# Board_2.net
KiCad netlist of a schematic drawn in EAGLE
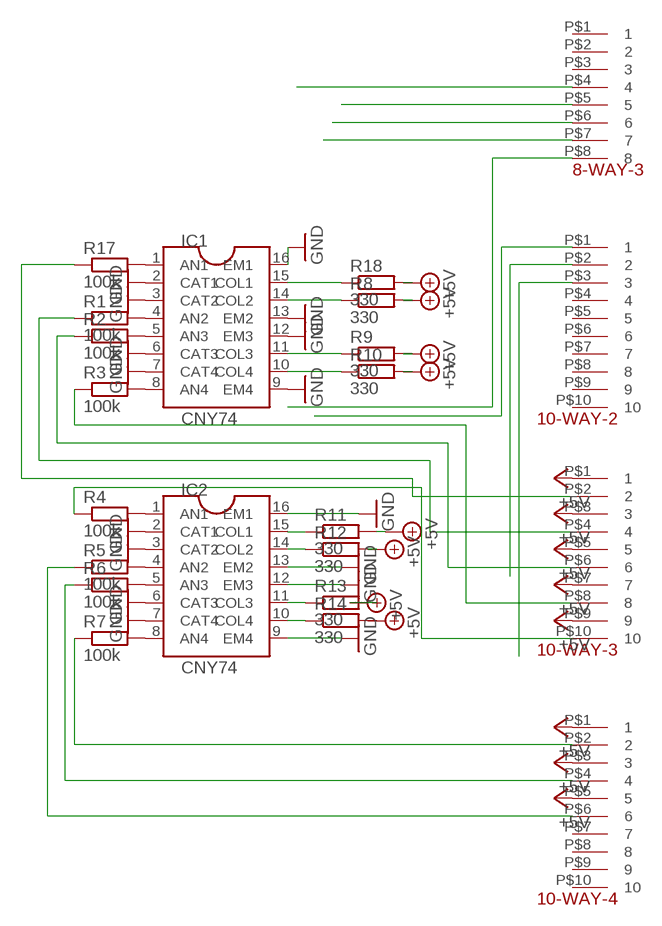
[diagram p0: schematic, sheet 1]

(export (version "E")
  (design (tool "Eeschema 10.0.6"))
  (components
    (comp (ref "8-WAY-3")
      (value "SDH8PIN")
      (footprint "eagle-import:SDH8PIN")
      (libsource (lib "eagle-import") (part "SDH8PIN"))
    )
    (comp (ref "10-WAY-2")
      (value "SDH10PIN")
      (footprint "eagle-import:SDH10PIN")
      (libsource (lib "eagle-import") (part "SDH10PIN"))
    )
    (comp (ref "10-WAY-3")
      (value "SDH10PIN")
      (footprint "eagle-import:SDH10PIN")
      (libsource (lib "eagle-import") (part "SDH10PIN"))
    )
    (comp (ref "10-WAY-4")
      (value "SDH10PIN")
      (footprint "eagle-import:SDH10PIN")
      (libsource (lib "eagle-import") (part "SDH10PIN"))
    )
    (comp (ref "IC1")
      (value "IC-CNY74-16DIL")
      (footprint "eagle-import:IC-CNY74-16DIL")
      (libsource (lib "eagle-import") (part "IC-CNY74-16DIL"))
    )
    (comp (ref "IC2")
      (value "IC-CNY74-16DIL")
      (footprint "eagle-import:IC-CNY74-16DIL")
      (libsource (lib "eagle-import") (part "IC-CNY74-16DIL"))
    )
    (comp (ref "R1")
      (value "100k")
      (footprint "eagle-import:P0613V")
      (libsource (lib "eagle-import") (part "R-EU_0613/5V"))
    )
    (comp (ref "R2")
      (value "100k")
      (footprint "eagle-import:P0613V")
      (libsource (lib "eagle-import") (part "R-EU_0613/5V"))
    )
    (comp (ref "R3")
      (value "100k")
      (footprint "eagle-import:P0613V")
      (libsource (lib "eagle-import") (part "R-EU_0613/5V"))
    )
    (comp (ref "R4")
      (value "100k")
      (footprint "eagle-import:P0613V")
      (libsource (lib "eagle-import") (part "R-EU_0613/5V"))
    )
    (comp (ref "R5")
      (value "100k")
      (footprint "eagle-import:P0613V")
      (libsource (lib "eagle-import") (part "R-EU_0613/5V"))
    )
    (comp (ref "R6")
      (value "100k")
      (footprint "eagle-import:P0613V")
      (libsource (lib "eagle-import") (part "R-EU_0613/5V"))
    )
    (comp (ref "R7")
      (value "100k")
      (footprint "eagle-import:P0613V")
      (libsource (lib "eagle-import") (part "R-EU_0613/5V"))
    )
    (comp (ref "R8")
      (value "330")
      (footprint "eagle-import:P0613V")
      (libsource (lib "eagle-import") (part "R-EU_0613/5V"))
    )
    (comp (ref "R9")
      (value "330")
      (footprint "eagle-import:P0613V")
      (libsource (lib "eagle-import") (part "R-EU_0613/5V"))
    )
    (comp (ref "R10")
      (value "330")
      (footprint "eagle-import:P0613V")
      (libsource (lib "eagle-import") (part "R-EU_0613/5V"))
    )
    (comp (ref "R11")
      (value "330")
      (footprint "eagle-import:P0613V")
      (libsource (lib "eagle-import") (part "R-EU_0613/5V"))
    )
    (comp (ref "R12")
      (value "330")
      (footprint "eagle-import:P0613V")
      (libsource (lib "eagle-import") (part "R-EU_0613/5V"))
    )
    (comp (ref "R13")
      (value "330")
      (footprint "eagle-import:P0613V")
      (libsource (lib "eagle-import") (part "R-EU_0613/5V"))
    )
    (comp (ref "R14")
      (value "330")
      (footprint "eagle-import:P0613V")
      (libsource (lib "eagle-import") (part "R-EU_0613/5V"))
    )
    (comp (ref "R17")
      (value "100k")
      (footprint "eagle-import:P0613V")
      (libsource (lib "eagle-import") (part "R-EU_0613/5V"))
    )
    (comp (ref "R18")
      (value "330")
      (footprint "eagle-import:P0613V")
      (libsource (lib "eagle-import") (part "R-EU_0613/5V"))
    )
  )
  (nets
    (net (code "1") (name "+5V") (class "Default")
      (node (ref "10-WAY-3") (pin "P$1") (pinfunction "1_P$1") (pintype "bidirectional"))
      (node (ref "10-WAY-3") (pin "P$3") (pinfunction "3_P$3") (pintype "bidirectional"))
      (node (ref "10-WAY-3") (pin "P$5") (pinfunction "5_P$5") (pintype "bidirectional"))
      (node (ref "10-WAY-3") (pin "P$7") (pinfunction "7_P$7") (pintype "bidirectional"))
      (node (ref "10-WAY-3") (pin "P$9") (pinfunction "9_P$9") (pintype "bidirectional"))
      (node (ref "10-WAY-4") (pin "P$1") (pinfunction "1_P$1") (pintype "bidirectional"))
      (node (ref "10-WAY-4") (pin "P$3") (pinfunction "3_P$3") (pintype "bidirectional"))
      (node (ref "10-WAY-4") (pin "P$5") (pinfunction "5_P$5") (pintype "bidirectional"))
      (node (ref "R10") (pin "2") (pinfunction "2_2") (pintype "passive"))
      (node (ref "R11") (pin "2") (pinfunction "2_2") (pintype "passive"))
      (node (ref "R12") (pin "2") (pinfunction "2_2") (pintype "passive"))
      (node (ref "R13") (pin "2") (pinfunction "2_2") (pintype "passive"))
      (node (ref "R18") (pin "2") (pinfunction "2_2") (pintype "passive"))
      (node (ref "R8") (pin "2") (pinfunction "2_2") (pintype "passive"))
      (node (ref "R9") (pin "2") (pinfunction "2_2") (pintype "passive"))
    )
    (net (code "2") (name "GND") (class "Default")
      (node (ref "IC1") (pin "12") (pinfunction "EM3_12") (pintype "bidirectional"))
      (node (ref "IC1") (pin "13") (pinfunction "EM2_13") (pintype "bidirectional"))
      (node (ref "IC1") (pin "16") (pinfunction "EM1_16") (pintype "bidirectional"))
      (node (ref "IC1") (pin "2") (pinfunction "CAT1_2") (pintype "bidirectional"))
      (node (ref "IC1") (pin "3") (pinfunction "CAT2_3") (pintype "bidirectional"))
      (node (ref "IC1") (pin "6") (pinfunction "CAT3_6") (pintype "bidirectional"))
      (node (ref "IC1") (pin "7") (pinfunction "CAT4_7") (pintype "bidirectional"))
      (node (ref "IC1") (pin "9") (pinfunction "EM4_9") (pintype "bidirectional"))
      (node (ref "IC2") (pin "12") (pinfunction "EM3_12") (pintype "bidirectional"))
      (node (ref "IC2") (pin "13") (pinfunction "EM2_13") (pintype "bidirectional"))
      (node (ref "IC2") (pin "16") (pinfunction "EM1_16") (pintype "bidirectional"))
      (node (ref "IC2") (pin "2") (pinfunction "CAT1_2") (pintype "bidirectional"))
      (node (ref "IC2") (pin "3") (pinfunction "CAT2_3") (pintype "bidirectional"))
      (node (ref "IC2") (pin "6") (pinfunction "CAT3_6") (pintype "bidirectional"))
      (node (ref "IC2") (pin "7") (pinfunction "CAT4_7") (pintype "bidirectional"))
      (node (ref "IC2") (pin "9") (pinfunction "EM4_9") (pintype "bidirectional"))
    )
    (net (code "3") (name "Net-(10-WAY-3-2)") (class "Default")
      (node (ref "10-WAY-3") (pin "P$2") (pinfunction "2_P$2") (pintype "bidirectional"))
      (node (ref "R17") (pin "1") (pinfunction "1_1") (pintype "passive"))
    )
    (net (code "4") (name "Net-(10-WAY-3-4)") (class "Default")
      (node (ref "10-WAY-3") (pin "P$4") (pinfunction "4_P$4") (pintype "bidirectional"))
      (node (ref "R1") (pin "1") (pinfunction "1_1") (pintype "passive"))
    )
    (net (code "5") (name "Net-(10-WAY-3-6)") (class "Default")
      (node (ref "10-WAY-3") (pin "P$6") (pinfunction "6_P$6") (pintype "bidirectional"))
      (node (ref "R2") (pin "1") (pinfunction "1_1") (pintype "passive"))
    )
    (net (code "6") (name "Net-(10-WAY-3-8)") (class "Default")
      (node (ref "10-WAY-3") (pin "P$8") (pinfunction "8_P$8") (pintype "bidirectional"))
      (node (ref "R3") (pin "1") (pinfunction "1_1") (pintype "passive"))
    )
    (net (code "7") (name "Net-(10-WAY-3-10)") (class "Default")
      (node (ref "10-WAY-3") (pin "P$10") (pinfunction "10_P$10") (pintype "bidirectional"))
      (node (ref "R4") (pin "1") (pinfunction "1_1") (pintype "passive"))
    )
    (net (code "8") (name "Net-(10-WAY-4-2)") (class "Default")
      (node (ref "10-WAY-4") (pin "P$2") (pinfunction "2_P$2") (pintype "bidirectional"))
      (node (ref "R7") (pin "1") (pinfunction "1_1") (pintype "passive"))
    )
    (net (code "9") (name "Net-(10-WAY-4-4)") (class "Default")
      (node (ref "10-WAY-4") (pin "P$4") (pinfunction "4_P$4") (pintype "bidirectional"))
      (node (ref "R6") (pin "1") (pinfunction "1_1") (pintype "passive"))
    )
    (net (code "10") (name "Net-(10-WAY-4-6)") (class "Default")
      (node (ref "10-WAY-4") (pin "P$6") (pinfunction "6_P$6") (pintype "bidirectional"))
      (node (ref "R5") (pin "1") (pinfunction "1_1") (pintype "passive"))
    )
    (net (code "11") (name "Net-(IC1-AN1)") (class "Default")
      (node (ref "IC1") (pin "1") (pinfunction "AN1_1") (pintype "bidirectional"))
      (node (ref "R17") (pin "2") (pinfunction "2_2") (pintype "passive"))
    )
    (net (code "12") (name "Net-(IC1-AN2)") (class "Default")
      (node (ref "IC1") (pin "4") (pinfunction "AN2_4") (pintype "bidirectional"))
      (node (ref "R1") (pin "2") (pinfunction "2_2") (pintype "passive"))
    )
    (net (code "13") (name "Net-(IC1-AN3)") (class "Default")
      (node (ref "IC1") (pin "5") (pinfunction "AN3_5") (pintype "bidirectional"))
      (node (ref "R2") (pin "2") (pinfunction "2_2") (pintype "passive"))
    )
    (net (code "14") (name "Net-(IC1-AN4)") (class "Default")
      (node (ref "IC1") (pin "8") (pinfunction "AN4_8") (pintype "bidirectional"))
      (node (ref "R3") (pin "2") (pinfunction "2_2") (pintype "passive"))
    )
    (net (code "15") (name "Net-(IC1-COL1)") (class "Default")
      (node (ref "IC1") (pin "15") (pinfunction "COL1_15") (pintype "bidirectional"))
      (node (ref "R18") (pin "1") (pinfunction "1_1") (pintype "passive"))
    )
    (net (code "16") (name "Net-(IC1-COL2)") (class "Default")
      (node (ref "IC1") (pin "14") (pinfunction "COL2_14") (pintype "bidirectional"))
      (node (ref "R8") (pin "1") (pinfunction "1_1") (pintype "passive"))
    )
    (net (code "17") (name "Net-(IC1-COL3)") (class "Default")
      (node (ref "IC1") (pin "11") (pinfunction "COL3_11") (pintype "bidirectional"))
      (node (ref "R9") (pin "1") (pinfunction "1_1") (pintype "passive"))
    )
    (net (code "18") (name "Net-(IC1-COL4)") (class "Default")
      (node (ref "IC1") (pin "10") (pinfunction "COL4_10") (pintype "bidirectional"))
      (node (ref "R10") (pin "1") (pinfunction "1_1") (pintype "passive"))
    )
    (net (code "19") (name "Net-(IC2-AN1)") (class "Default")
      (node (ref "IC2") (pin "1") (pinfunction "AN1_1") (pintype "bidirectional"))
      (node (ref "R4") (pin "2") (pinfunction "2_2") (pintype "passive"))
    )
    (net (code "20") (name "Net-(IC2-AN2)") (class "Default")
      (node (ref "IC2") (pin "4") (pinfunction "AN2_4") (pintype "bidirectional"))
      (node (ref "R5") (pin "2") (pinfunction "2_2") (pintype "passive"))
    )
    (net (code "21") (name "Net-(IC2-AN3)") (class "Default")
      (node (ref "IC2") (pin "5") (pinfunction "AN3_5") (pintype "bidirectional"))
      (node (ref "R6") (pin "2") (pinfunction "2_2") (pintype "passive"))
    )
    (net (code "22") (name "Net-(IC2-AN4)") (class "Default")
      (node (ref "IC2") (pin "8") (pinfunction "AN4_8") (pintype "bidirectional"))
      (node (ref "R7") (pin "2") (pinfunction "2_2") (pintype "passive"))
    )
    (net (code "23") (name "Net-(IC2-COL1)") (class "Default")
      (node (ref "IC2") (pin "15") (pinfunction "COL1_15") (pintype "bidirectional"))
      (node (ref "R11") (pin "1") (pinfunction "1_1") (pintype "passive"))
    )
    (net (code "24") (name "Net-(IC2-COL2)") (class "Default")
      (node (ref "IC2") (pin "14") (pinfunction "COL2_14") (pintype "bidirectional"))
      (node (ref "R12") (pin "1") (pinfunction "1_1") (pintype "passive"))
    )
    (net (code "25") (name "Net-(IC2-COL3)") (class "Default")
      (node (ref "IC2") (pin "11") (pinfunction "COL3_11") (pintype "bidirectional"))
      (node (ref "R13") (pin "1") (pinfunction "1_1") (pintype "passive"))
    )
    (net (code "26") (name "Net-(IC2-COL4)") (class "Default")
      (node (ref "IC2") (pin "10") (pinfunction "COL4_10") (pintype "bidirectional"))
      (node (ref "R14") (pin "1") (pinfunction "1_1") (pintype "passive"))
    )
    (net (code "27") (name "unconnected-(8-WAY-3-1-PadP$1)") (class "Default")
      (node (ref "8-WAY-3") (pin "P$1") (pinfunction "1_P$1") (pintype "bidirectional"))
    )
    (net (code "28") (name "unconnected-(8-WAY-3-2-PadP$2)") (class "Default")
      (node (ref "8-WAY-3") (pin "P$2") (pinfunction "2_P$2") (pintype "bidirectional"))
    )
    (net (code "29") (name "unconnected-(8-WAY-3-3-PadP$3)") (class "Default")
      (node (ref "8-WAY-3") (pin "P$3") (pinfunction "3_P$3") (pintype "bidirectional"))
    )
    (net (code "30") (name "unconnected-(8-WAY-3-4-PadP$4)") (class "Default")
      (node (ref "8-WAY-3") (pin "P$4") (pinfunction "4_P$4") (pintype "bidirectional"))
    )
    (net (code "31") (name "unconnected-(8-WAY-3-5-PadP$5)") (class "Default")
      (node (ref "8-WAY-3") (pin "P$5") (pinfunction "5_P$5") (pintype "bidirectional"))
    )
    (net (code "32") (name "unconnected-(8-WAY-3-6-PadP$6)") (class "Default")
      (node (ref "8-WAY-3") (pin "P$6") (pinfunction "6_P$6") (pintype "bidirectional"))
    )
    (net (code "33") (name "unconnected-(8-WAY-3-7-PadP$7)") (class "Default")
      (node (ref "8-WAY-3") (pin "P$7") (pinfunction "7_P$7") (pintype "bidirectional"))
    )
    (net (code "34") (name "unconnected-(8-WAY-3-8-PadP$8)") (class "Default")
      (node (ref "8-WAY-3") (pin "P$8") (pinfunction "8_P$8") (pintype "bidirectional"))
    )
    (net (code "35") (name "unconnected-(10-WAY-2-1-PadP$1)") (class "Default")
      (node (ref "10-WAY-2") (pin "P$1") (pinfunction "1_P$1") (pintype "bidirectional"))
    )
    (net (code "36") (name "unconnected-(10-WAY-2-2-PadP$2)") (class "Default")
      (node (ref "10-WAY-2") (pin "P$2") (pinfunction "2_P$2") (pintype "bidirectional"))
    )
    (net (code "37") (name "unconnected-(10-WAY-2-3-PadP$3)") (class "Default")
      (node (ref "10-WAY-2") (pin "P$3") (pinfunction "3_P$3") (pintype "bidirectional"))
    )
    (net (code "38") (name "unconnected-(10-WAY-2-4-PadP$4)") (class "Default")
      (node (ref "10-WAY-2") (pin "P$4") (pinfunction "4_P$4") (pintype "bidirectional"))
    )
    (net (code "39") (name "unconnected-(10-WAY-2-5-PadP$5)") (class "Default")
      (node (ref "10-WAY-2") (pin "P$5") (pinfunction "5_P$5") (pintype "bidirectional"))
    )
    (net (code "40") (name "unconnected-(10-WAY-2-6-PadP$6)") (class "Default")
      (node (ref "10-WAY-2") (pin "P$6") (pinfunction "6_P$6") (pintype "bidirectional"))
    )
    (net (code "41") (name "unconnected-(10-WAY-2-7-PadP$7)") (class "Default")
      (node (ref "10-WAY-2") (pin "P$7") (pinfunction "7_P$7") (pintype "bidirectional"))
    )
    (net (code "42") (name "unconnected-(10-WAY-2-8-PadP$8)") (class "Default")
      (node (ref "10-WAY-2") (pin "P$8") (pinfunction "8_P$8") (pintype "bidirectional"))
    )
    (net (code "43") (name "unconnected-(10-WAY-2-9-PadP$9)") (class "Default")
      (node (ref "10-WAY-2") (pin "P$9") (pinfunction "9_P$9") (pintype "bidirectional"))
    )
    (net (code "44") (name "unconnected-(10-WAY-2-10-PadP$10)") (class "Default")
      (node (ref "10-WAY-2") (pin "P$10") (pinfunction "10_P$10") (pintype "bidirectional"))
    )
    (net (code "45") (name "unconnected-(10-WAY-4-7-PadP$7)") (class "Default")
      (node (ref "10-WAY-4") (pin "P$7") (pinfunction "7_P$7") (pintype "bidirectional"))
    )
    (net (code "46") (name "unconnected-(10-WAY-4-8-PadP$8)") (class "Default")
      (node (ref "10-WAY-4") (pin "P$8") (pinfunction "8_P$8") (pintype "bidirectional"))
    )
    (net (code "47") (name "unconnected-(10-WAY-4-9-PadP$9)") (class "Default")
      (node (ref "10-WAY-4") (pin "P$9") (pinfunction "9_P$9") (pintype "bidirectional"))
    )
    (net (code "48") (name "unconnected-(10-WAY-4-10-PadP$10)") (class "Default")
      (node (ref "10-WAY-4") (pin "P$10") (pinfunction "10_P$10") (pintype "bidirectional"))
    )
    (net (code "49") (name "unconnected-(R14-Pad2)") (class "Default")
      (node (ref "R14") (pin "2") (pinfunction "2_2") (pintype "passive"))
    )
  )
)
